# 40_MCU.net
KiCad netlist of a schematic drawn in Altium Designer
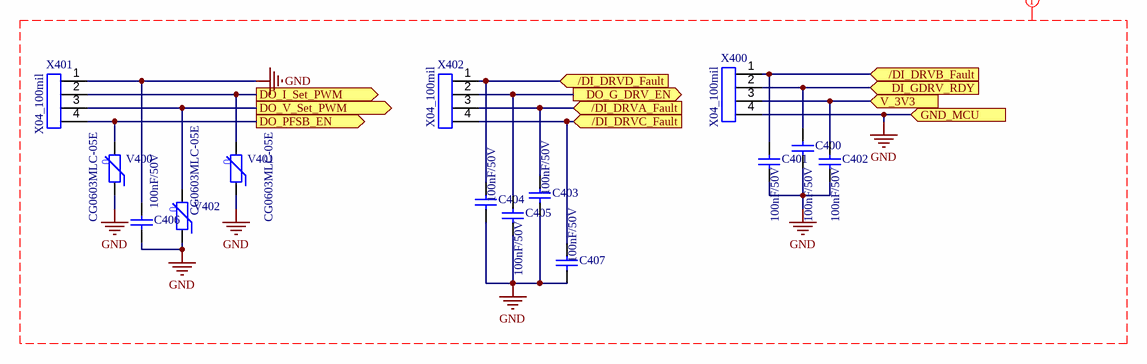
[diagram p0: 40_MCU.SchDoc]

(export (version "E")
  (design (tool "Eeschema 10.0.6"))
  (components
    (comp (ref "C400")
      (value "100nF/50V")
      (footprint "EIA0603")
      (description "Generic 0603 ceramic capacitor")
      (fields (field (name "MANUFACTURER") "Open") (field (name "CREATED BY") "Hamad"))
      (libsource (lib "Amjad_Components") (part "C_Ceramic"))
    )
    (comp (ref "C401")
      (value "100nF/50V")
      (footprint "EIA0603")
      (description "Generic 0603 ceramic capacitor")
      (fields (field (name "MANUFACTURER") "Open") (field (name "CREATED BY") "Hamad"))
      (libsource (lib "Amjad_Components") (part "C_Ceramic"))
    )
    (comp (ref "C402")
      (value "100nF/50V")
      (footprint "EIA0603")
      (description "Generic 0603 ceramic capacitor")
      (fields (field (name "MANUFACTURER") "Open") (field (name "CREATED BY") "Hamad"))
      (libsource (lib "Amjad_Components") (part "C_Ceramic"))
    )
    (comp (ref "C403")
      (value "100nF/50V")
      (footprint "EIA0603")
      (description "Generic 0603 ceramic capacitor")
      (fields (field (name "MANUFACTURER") "Open") (field (name "CREATED BY") "Hamad"))
      (libsource (lib "Amjad_Components") (part "C_Ceramic"))
    )
    (comp (ref "C404")
      (value "100nF/50V")
      (footprint "EIA0603")
      (description "Generic 0603 ceramic capacitor")
      (fields (field (name "MANUFACTURER") "Open") (field (name "CREATED BY") "Hamad"))
      (libsource (lib "Amjad_Components") (part "C_Ceramic"))
    )
    (comp (ref "C405")
      (value "100nF/50V")
      (footprint "EIA0603")
      (description "Generic 0603 ceramic capacitor")
      (fields (field (name "MANUFACTURER") "Open") (field (name "CREATED BY") "Hamad"))
      (libsource (lib "Amjad_Components") (part "C_Ceramic"))
    )
    (comp (ref "C406")
      (value "100nF/50V")
      (footprint "EIA0603")
      (description "Generic 0603 ceramic capacitor")
      (fields (field (name "MANUFACTURER") "Open") (field (name "CREATED BY") "Hamad"))
      (libsource (lib "Amjad_Components") (part "C_Ceramic"))
    )
    (comp (ref "C407")
      (value "100nF/50V")
      (footprint "EIA0603")
      (description "Generic 0603 ceramic capacitor")
      (fields (field (name "MANUFACTURER") "Open") (field (name "CREATED BY") "Hamad"))
      (libsource (lib "Amjad_Components") (part "C_Ceramic"))
    )
    (comp (ref "V400")
      (value "CG0603MLC-05E")
      (footprint "EIA0603")
      (description "Bidirectional 5V, 25V 0603 Diodes - ESD RoHS")
      (fields (field (name "MANUFACTURER") "Bourne Semicon") (field (name "CREATED BY") "HamadA"))
      (libsource (lib "Amjad_Components") (part "Varistor"))
    )
    (comp (ref "V401")
      (value "CG0603MLC-05E")
      (footprint "EIA0603")
      (description "Bidirectional 5V, 25V 0603 Diodes - ESD RoHS")
      (fields (field (name "MANUFACTURER") "Bourne Semicon") (field (name "CREATED BY") "HamadA"))
      (libsource (lib "Amjad_Components") (part "Varistor"))
    )
    (comp (ref "V402")
      (value "CG0603MLC-05E")
      (footprint "EIA0603")
      (description "Bidirectional 5V, 25V 0603 Diodes - ESD RoHS")
      (fields (field (name "MANUFACTURER") "Bourne Semicon") (field (name "CREATED BY") "HamadA"))
      (libsource (lib "Amjad_Components") (part "Varistor"))
    )
    (comp (ref "X400")
      (value "X04_100mil")
      (footprint "X04_100mil")
      (description "4 Pin THT Connector 100 mil pitch")
      (fields (field (name "MANUFACTURER") "3M") (field (name "CREATED BY") "Hamad"))
      (libsource (lib "Amjad_Components") (part "X04"))
    )
    (comp (ref "X401")
      (value "X04_100mil")
      (footprint "X04_100mil")
      (description "4 Pin THT Connector 100 mil pitch")
      (fields (field (name "MANUFACTURER") "3M") (field (name "CREATED BY") "Hamad"))
      (libsource (lib "Amjad_Components") (part "X04"))
    )
    (comp (ref "X402")
      (value "X04_100mil")
      (footprint "X04_100mil")
      (description "4 Pin THT Connector 100 mil pitch")
      (fields (field (name "MANUFACTURER") "3M") (field (name "CREATED BY") "Hamad"))
      (libsource (lib "Amjad_Components") (part "X04"))
    )
  )
  (nets
    (net (code "1") (name "/DI_GDRV_RDY") (class "Default")
      (node (ref "C400") (pin "2") (pinfunction "2_2") (pintype "passive"))
      (node (ref "X400") (pin "2") (pintype "passive"))
    )
    (net (code "2") (name "/DO_G_DRV_EN") (class "Default")
      (node (ref "C405") (pin "2") (pinfunction "2_2") (pintype "passive"))
      (node (ref "X402") (pin "2") (pintype "passive"))
    )
    (net (code "3") (name "/DO_I_Set_PWM") (class "Default")
      (node (ref "V401") (pin "2") (pintype "passive"))
      (node (ref "X401") (pin "2") (pintype "passive"))
    )
    (net (code "4") (name "/DO_PFSB_EN") (class "Default")
      (node (ref "V400") (pin "2") (pintype "passive"))
      (node (ref "X401") (pin "4") (pintype "passive"))
    )
    (net (code "5") (name "/DO_V_Set_PWM") (class "Default")
      (node (ref "V402") (pin "2") (pintype "passive"))
      (node (ref "X401") (pin "3") (pintype "passive"))
    )
    (net (code "6") (name "/V_3V3") (class "Default")
      (node (ref "C402") (pin "2") (pinfunction "2_2") (pintype "passive"))
      (node (ref "X400") (pin "3") (pintype "passive"))
    )
    (net (code "7") (name "/{slash}DI_DRVA_Fault") (class "Default")
      (node (ref "C403") (pin "2") (pinfunction "2_2") (pintype "passive"))
      (node (ref "X402") (pin "3") (pintype "passive"))
    )
    (net (code "8") (name "/{slash}DI_DRVB_Fault") (class "Default")
      (node (ref "C401") (pin "2") (pinfunction "2_2") (pintype "passive"))
      (node (ref "X400") (pin "1") (pintype "passive"))
    )
    (net (code "9") (name "/{slash}DI_DRVC_Fault") (class "Default")
      (node (ref "C407") (pin "2") (pinfunction "2_2") (pintype "passive"))
      (node (ref "X402") (pin "4") (pintype "passive"))
    )
    (net (code "10") (name "/{slash}DI_DRVD_Fault") (class "Default")
      (node (ref "C404") (pin "2") (pinfunction "2_2") (pintype "passive"))
      (node (ref "X402") (pin "1") (pintype "passive"))
    )
    (net (code "11") (name "GND") (class "Default")
      (node (ref "C400") (pin "1") (pinfunction "1_1") (pintype "passive"))
      (node (ref "C401") (pin "1") (pinfunction "1_1") (pintype "passive"))
      (node (ref "C402") (pin "1") (pinfunction "1_1") (pintype "passive"))
      (node (ref "C403") (pin "1") (pinfunction "1_1") (pintype "passive"))
      (node (ref "C404") (pin "1") (pinfunction "1_1") (pintype "passive"))
      (node (ref "C405") (pin "1") (pinfunction "1_1") (pintype "passive"))
      (node (ref "C406") (pin "1") (pinfunction "1_1") (pintype "passive"))
      (node (ref "C406") (pin "2") (pinfunction "2_2") (pintype "passive"))
      (node (ref "C407") (pin "1") (pinfunction "1_1") (pintype "passive"))
      (node (ref "V400") (pin "1") (pintype "passive"))
      (node (ref "V401") (pin "1") (pintype "passive"))
      (node (ref "V402") (pin "1") (pintype "passive"))
      (node (ref "X400") (pin "4") (pintype "passive"))
      (node (ref "X401") (pin "1") (pintype "passive"))
    )
  )
)
